# TEENSY_3.net
KiCad netlist of a schematic drawn in Altium Designer
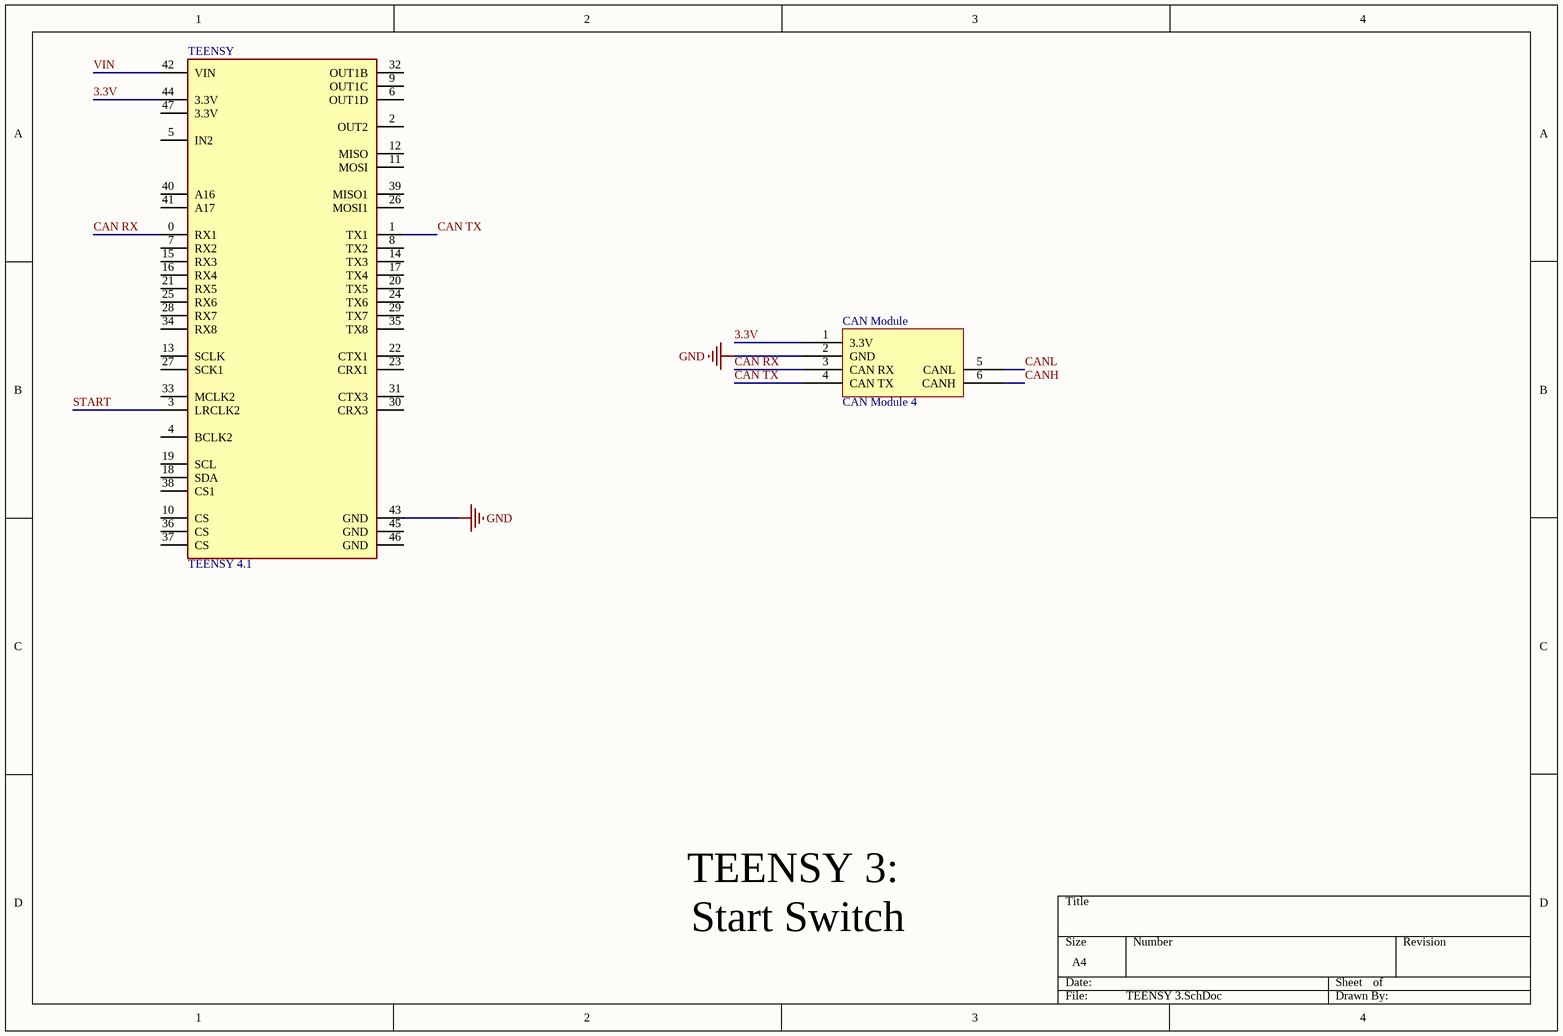
[diagram p0: TEENSY 3.SchDoc]

(export (version "E")
  (design (tool "Eeschema 10.0.6"))
  (components
    (comp (ref "CAN Module")
      (value "CAN Module 4")
      (footprint "CAN Module-Footprint-1")
      (description "CAN waveshare")
      (libsource (lib "cmabey15") (part "CAN Module-Symbol-1"))
    )
    (comp (ref "TEENSY")
      (value "TEENSY 4.1")
      (footprint "FP-DEV-16996-MFG")
      (description "TEENSY 4.1 (HEADERS)")
      (libsource (lib "Altium Content Vault") (part "080115a1ce54750370cf87ec145ee29"))
    )
  )
  (nets
    (net (code "1") (name "/3.3V") (class "Default")
      (node (ref "CAN Module") (pin "1") (pinfunction "3.3V_1") (pintype "passive"))
      (node (ref "TEENSY") (pin "44") (pinfunction "3.3V_44") (pintype "passive"))
    )
    (net (code "2") (name "/CAN RX") (class "Default")
      (node (ref "CAN Module") (pin "3") (pinfunction "CAN_RX_3") (pintype "passive"))
      (node (ref "TEENSY") (pin "0") (pinfunction "RX1_0") (pintype "passive"))
    )
    (net (code "3") (name "/CAN TX") (class "Default")
      (node (ref "CAN Module") (pin "4") (pinfunction "CAN_TX_4") (pintype "passive"))
      (node (ref "TEENSY") (pin "1") (pinfunction "TX1_1") (pintype "passive"))
    )
    (net (code "4") (name "/CANH") (class "Default")
      (node (ref "CAN Module") (pin "6") (pinfunction "CANH_6") (pintype "passive"))
    )
    (net (code "5") (name "/CANL") (class "Default")
      (node (ref "CAN Module") (pin "5") (pinfunction "CANL_5") (pintype "passive"))
    )
    (net (code "6") (name "/START") (class "Default")
      (node (ref "TEENSY") (pin "3") (pinfunction "LRCLK2_3") (pintype "passive"))
    )
    (net (code "7") (name "/VIN") (class "Default")
      (node (ref "TEENSY") (pin "42") (pinfunction "VIN_42") (pintype "passive"))
    )
    (net (code "8") (name "GND") (class "Default")
      (node (ref "CAN Module") (pin "2") (pinfunction "GND_2") (pintype "passive"))
      (node (ref "TEENSY") (pin "43") (pinfunction "GND_43") (pintype "passive"))
    )
    (net (code "9") (name "unconnected-(TEENSY-3.3V-Pad47)") (class "Default")
      (node (ref "TEENSY") (pin "47") (pinfunction "3.3V_47") (pintype "passive"))
    )
    (net (code "10") (name "unconnected-(TEENSY-A16-Pad40)") (class "Default")
      (node (ref "TEENSY") (pin "40") (pinfunction "A16_40") (pintype "passive"))
    )
    (net (code "11") (name "unconnected-(TEENSY-A17-Pad41)") (class "Default")
      (node (ref "TEENSY") (pin "41") (pinfunction "A17_41") (pintype "passive"))
    )
    (net (code "12") (name "unconnected-(TEENSY-BCLK2-Pad4)") (class "Default")
      (node (ref "TEENSY") (pin "4") (pinfunction "BCLK2_4") (pintype "passive"))
    )
    (net (code "13") (name "unconnected-(TEENSY-CRX1-Pad23)") (class "Default")
      (node (ref "TEENSY") (pin "23") (pinfunction "CRX1_23") (pintype "passive"))
    )
    (net (code "14") (name "unconnected-(TEENSY-CRX3-Pad30)") (class "Default")
      (node (ref "TEENSY") (pin "30") (pinfunction "CRX3_30") (pintype "passive"))
    )
    (net (code "15") (name "unconnected-(TEENSY-CS-Pad10)") (class "Default")
      (node (ref "TEENSY") (pin "10") (pinfunction "CS_10") (pintype "passive"))
    )
    (net (code "16") (name "unconnected-(TEENSY-CS-Pad36)") (class "Default")
      (node (ref "TEENSY") (pin "36") (pinfunction "CS_36") (pintype "passive"))
    )
    (net (code "17") (name "unconnected-(TEENSY-CS-Pad37)") (class "Default")
      (node (ref "TEENSY") (pin "37") (pinfunction "CS_37") (pintype "passive"))
    )
    (net (code "18") (name "unconnected-(TEENSY-CS1-Pad38)") (class "Default")
      (node (ref "TEENSY") (pin "38") (pinfunction "CS1_38") (pintype "passive"))
    )
    (net (code "19") (name "unconnected-(TEENSY-CTX1-Pad22)") (class "Default")
      (node (ref "TEENSY") (pin "22") (pinfunction "CTX1_22") (pintype "passive"))
    )
    (net (code "20") (name "unconnected-(TEENSY-CTX3-Pad31)") (class "Default")
      (node (ref "TEENSY") (pin "31") (pinfunction "CTX3_31") (pintype "passive"))
    )
    (net (code "21") (name "unconnected-(TEENSY-GND-Pad45)") (class "Default")
      (node (ref "TEENSY") (pin "45") (pinfunction "GND_45") (pintype "passive"))
    )
    (net (code "22") (name "unconnected-(TEENSY-GND-Pad46)") (class "Default")
      (node (ref "TEENSY") (pin "46") (pinfunction "GND_46") (pintype "passive"))
    )
    (net (code "23") (name "unconnected-(TEENSY-IN2-Pad5)") (class "Default")
      (node (ref "TEENSY") (pin "5") (pinfunction "IN2_5") (pintype "passive"))
    )
    (net (code "24") (name "unconnected-(TEENSY-MCLK2-Pad33)") (class "Default")
      (node (ref "TEENSY") (pin "33") (pinfunction "MCLK2_33") (pintype "passive"))
    )
    (net (code "25") (name "unconnected-(TEENSY-MISO-Pad12)") (class "Default")
      (node (ref "TEENSY") (pin "12") (pinfunction "MISO_12") (pintype "passive"))
    )
    (net (code "26") (name "unconnected-(TEENSY-MISO1-Pad39)") (class "Default")
      (node (ref "TEENSY") (pin "39") (pinfunction "MISO1_39") (pintype "passive"))
    )
    (net (code "27") (name "unconnected-(TEENSY-MOSI-Pad11)") (class "Default")
      (node (ref "TEENSY") (pin "11") (pinfunction "MOSI_11") (pintype "passive"))
    )
    (net (code "28") (name "unconnected-(TEENSY-MOSI1-Pad26)") (class "Default")
      (node (ref "TEENSY") (pin "26") (pinfunction "MOSI1_26") (pintype "passive"))
    )
    (net (code "29") (name "unconnected-(TEENSY-OUT1B-Pad32)") (class "Default")
      (node (ref "TEENSY") (pin "32") (pinfunction "OUT1B_32") (pintype "passive"))
    )
    (net (code "30") (name "unconnected-(TEENSY-OUT1C-Pad9)") (class "Default")
      (node (ref "TEENSY") (pin "9") (pinfunction "OUT1C_9") (pintype "passive"))
    )
    (net (code "31") (name "unconnected-(TEENSY-OUT1D-Pad6)") (class "Default")
      (node (ref "TEENSY") (pin "6") (pinfunction "OUT1D_6") (pintype "passive"))
    )
    (net (code "32") (name "unconnected-(TEENSY-OUT2-Pad2)") (class "Default")
      (node (ref "TEENSY") (pin "2") (pinfunction "OUT2_2") (pintype "passive"))
    )
    (net (code "33") (name "unconnected-(TEENSY-RX2-Pad7)") (class "Default")
      (node (ref "TEENSY") (pin "7") (pinfunction "RX2_7") (pintype "passive"))
    )
    (net (code "34") (name "unconnected-(TEENSY-RX3-Pad15)") (class "Default")
      (node (ref "TEENSY") (pin "15") (pinfunction "RX3_15") (pintype "passive"))
    )
    (net (code "35") (name "unconnected-(TEENSY-RX4-Pad16)") (class "Default")
      (node (ref "TEENSY") (pin "16") (pinfunction "RX4_16") (pintype "passive"))
    )
    (net (code "36") (name "unconnected-(TEENSY-RX5-Pad21)") (class "Default")
      (node (ref "TEENSY") (pin "21") (pinfunction "RX5_21") (pintype "passive"))
    )
    (net (code "37") (name "unconnected-(TEENSY-RX6-Pad25)") (class "Default")
      (node (ref "TEENSY") (pin "25") (pinfunction "RX6_25") (pintype "passive"))
    )
    (net (code "38") (name "unconnected-(TEENSY-RX7-Pad28)") (class "Default")
      (node (ref "TEENSY") (pin "28") (pinfunction "RX7_28") (pintype "passive"))
    )
    (net (code "39") (name "unconnected-(TEENSY-RX8-Pad34)") (class "Default")
      (node (ref "TEENSY") (pin "34") (pinfunction "RX8_34") (pintype "passive"))
    )
    (net (code "40") (name "unconnected-(TEENSY-SCK1-Pad27)") (class "Default")
      (node (ref "TEENSY") (pin "27") (pinfunction "SCK1_27") (pintype "passive"))
    )
    (net (code "41") (name "unconnected-(TEENSY-SCL-Pad19)") (class "Default")
      (node (ref "TEENSY") (pin "19") (pinfunction "SCL_19") (pintype "passive"))
    )
    (net (code "42") (name "unconnected-(TEENSY-SCLK-Pad13)") (class "Default")
      (node (ref "TEENSY") (pin "13") (pinfunction "SCLK_13") (pintype "passive"))
    )
    (net (code "43") (name "unconnected-(TEENSY-SDA-Pad18)") (class "Default")
      (node (ref "TEENSY") (pin "18") (pinfunction "SDA_18") (pintype "passive"))
    )
    (net (code "44") (name "unconnected-(TEENSY-TX2-Pad8)") (class "Default")
      (node (ref "TEENSY") (pin "8") (pinfunction "TX2_8") (pintype "passive"))
    )
    (net (code "45") (name "unconnected-(TEENSY-TX3-Pad14)") (class "Default")
      (node (ref "TEENSY") (pin "14") (pinfunction "TX3_14") (pintype "passive"))
    )
    (net (code "46") (name "unconnected-(TEENSY-TX4-Pad17)") (class "Default")
      (node (ref "TEENSY") (pin "17") (pinfunction "TX4_17") (pintype "passive"))
    )
    (net (code "47") (name "unconnected-(TEENSY-TX5-Pad20)") (class "Default")
      (node (ref "TEENSY") (pin "20") (pinfunction "TX5_20") (pintype "passive"))
    )
    (net (code "48") (name "unconnected-(TEENSY-TX6-Pad24)") (class "Default")
      (node (ref "TEENSY") (pin "24") (pinfunction "TX6_24") (pintype "passive"))
    )
    (net (code "49") (name "unconnected-(TEENSY-TX7-Pad29)") (class "Default")
      (node (ref "TEENSY") (pin "29") (pinfunction "TX7_29") (pintype "passive"))
    )
    (net (code "50") (name "unconnected-(TEENSY-TX8-Pad35)") (class "Default")
      (node (ref "TEENSY") (pin "35") (pinfunction "TX8_35") (pintype "passive"))
    )
  )
)
